# B9_HashBoard.net
KiCad netlist of a schematic drawn in Altium Designer
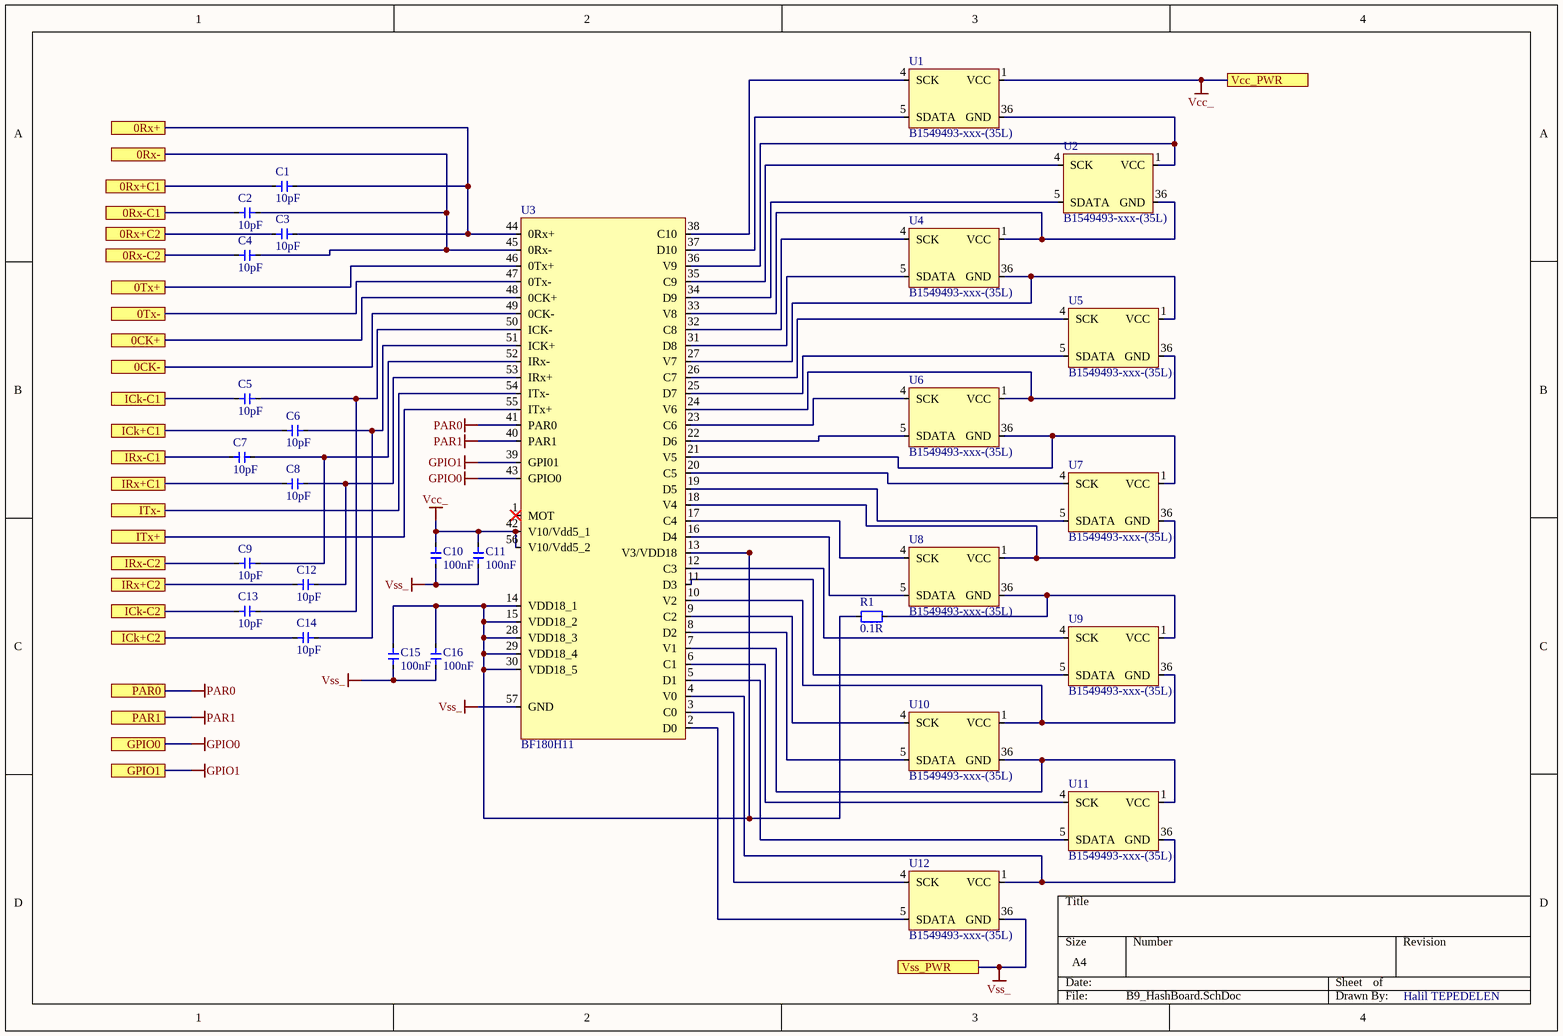
[diagram p0: B9_HashBoard.SchDoc]

(export (version "E")
  (design (tool "Eeschema 10.0.6"))
  (components
    (comp (ref "C1") (value "10pF") (footprint "C-0402R") (libsource (lib "B9_HashBoard") (part "10pF")))
    (comp (ref "C2") (value "10pF") (footprint "C-0402R") (libsource (lib "B9_HashBoard") (part "10pF")))
    (comp (ref "C3") (value "10pF") (footprint "C-0402R") (libsource (lib "B9_HashBoard") (part "10pF")))
    (comp (ref "C4") (value "10pF") (footprint "C-0402R") (libsource (lib "B9_HashBoard") (part "10pF")))
    (comp (ref "C5") (value "10pF") (footprint "C-0402R") (libsource (lib "B9_HashBoard") (part "10pF")))
    (comp (ref "C6") (value "10pF") (footprint "C-0402R") (libsource (lib "B9_HashBoard") (part "10pF")))
    (comp (ref "C7") (value "10pF") (footprint "C-0402R") (libsource (lib "B9_HashBoard") (part "10pF")))
    (comp (ref "C8") (value "10pF") (footprint "C-0402R") (libsource (lib "B9_HashBoard") (part "10pF")))
    (comp (ref "C9") (value "10pF") (footprint "C-0402R") (libsource (lib "B9_HashBoard") (part "10pF")))
    (comp (ref "C10") (value "100nF") (footprint "C-0402R") (libsource (lib "B9_HashBoard") (part "100nF")))
    (comp (ref "C11") (value "100nF") (footprint "C-0402R") (libsource (lib "B9_HashBoard") (part "100nF")))
    (comp (ref "C12") (value "10pF") (footprint "C-0402R") (libsource (lib "B9_HashBoard") (part "10pF")))
    (comp (ref "C13") (value "10pF") (footprint "C-0402R") (libsource (lib "B9_HashBoard") (part "10pF")))
    (comp (ref "C14") (value "10pF") (footprint "C-0402R") (libsource (lib "B9_HashBoard") (part "10pF")))
    (comp (ref "C15") (value "100nF") (footprint "C-0402R") (libsource (lib "B9_HashBoard") (part "100nF")))
    (comp (ref "C16") (value "100nF") (footprint "C-0402R") (libsource (lib "B9_HashBoard") (part "100nF")))
    (comp (ref "R1") (value "0.1R") (footprint "R-0402R") (libsource (lib "B9_HashBoard") (part "0.1R")))
    (comp (ref "U1")
      (value "B1549493-xxx-(35L)")
      (footprint "Bıtfury_Clarke_B1549493")
      (libsource (lib "B9_HashBoard") (part "B1549493-xxx-(35L)"))
    )
    (comp (ref "U2")
      (value "B1549493-xxx-(35L)")
      (footprint "Bıtfury_Clarke_B1549493")
      (libsource (lib "B9_HashBoard") (part "B1549493-xxx-(35L)"))
    )
    (comp (ref "U3")
      (value "BF180H11")
      (footprint "BF180H16")
      (libsource (lib "B9_HashBoard") (part "BF180H11"))
    )
    (comp (ref "U4")
      (value "B1549493-xxx-(35L)")
      (footprint "Bıtfury_Clarke_B1549493")
      (libsource (lib "B9_HashBoard") (part "B1549493-xxx-(35L)"))
    )
    (comp (ref "U5")
      (value "B1549493-xxx-(35L)")
      (footprint "Bıtfury_Clarke_B1549493")
      (libsource (lib "B9_HashBoard") (part "B1549493-xxx-(35L)"))
    )
    (comp (ref "U6")
      (value "B1549493-xxx-(35L)")
      (footprint "Bıtfury_Clarke_B1549493")
      (libsource (lib "B9_HashBoard") (part "B1549493-xxx-(35L)"))
    )
    (comp (ref "U7")
      (value "B1549493-xxx-(35L)")
      (footprint "Bıtfury_Clarke_B1549493")
      (libsource (lib "B9_HashBoard") (part "B1549493-xxx-(35L)"))
    )
    (comp (ref "U8")
      (value "B1549493-xxx-(35L)")
      (footprint "Bıtfury_Clarke_B1549493")
      (libsource (lib "B9_HashBoard") (part "B1549493-xxx-(35L)"))
    )
    (comp (ref "U9")
      (value "B1549493-xxx-(35L)")
      (footprint "Bıtfury_Clarke_B1549493")
      (libsource (lib "B9_HashBoard") (part "B1549493-xxx-(35L)"))
    )
    (comp (ref "U10")
      (value "B1549493-xxx-(35L)")
      (footprint "Bıtfury_Clarke_B1549493")
      (libsource (lib "B9_HashBoard") (part "B1549493-xxx-(35L)"))
    )
    (comp (ref "U11")
      (value "B1549493-xxx-(35L)")
      (footprint "Bıtfury_Clarke_B1549493")
      (libsource (lib "B9_HashBoard") (part "B1549493-xxx-(35L)"))
    )
    (comp (ref "U12")
      (value "B1549493-xxx-(35L)")
      (footprint "Bıtfury_Clarke_B1549493")
      (libsource (lib "B9_HashBoard") (part "B1549493-xxx-(35L)"))
    )
  )
  (nets
    (net (code "1") (name "/0CK+") (class "Default")
      (node (ref "U3") (pin "48") (pinfunction "0CK+_48") (pintype "passive"))
    )
    (net (code "2") (name "/0CK-") (class "Default")
      (node (ref "U3") (pin "49") (pinfunction "0CK-_49") (pintype "passive"))
    )
    (net (code "3") (name "/0Rx+") (class "Default")
      (node (ref "C1") (pin "2") (pinfunction "2_2") (pintype "passive"))
      (node (ref "C3") (pin "2") (pinfunction "2_2") (pintype "passive"))
      (node (ref "U3") (pin "44") (pinfunction "0Rx+_44") (pintype "passive"))
    )
    (net (code "4") (name "/0Rx+C1") (class "Default")
      (node (ref "C1") (pin "1") (pinfunction "1_1") (pintype "passive"))
    )
    (net (code "5") (name "/0Rx+C2") (class "Default")
      (node (ref "C3") (pin "1") (pinfunction "1_1") (pintype "passive"))
    )
    (net (code "6") (name "/0Rx-") (class "Default")
      (node (ref "C2") (pin "2") (pinfunction "2_2") (pintype "passive"))
      (node (ref "C4") (pin "2") (pinfunction "2_2") (pintype "passive"))
      (node (ref "U3") (pin "45") (pinfunction "0Rx-_45") (pintype "passive"))
    )
    (net (code "7") (name "/0Rx-C1") (class "Default")
      (node (ref "C2") (pin "1") (pinfunction "1_1") (pintype "passive"))
    )
    (net (code "8") (name "/0Rx-C2") (class "Default")
      (node (ref "C4") (pin "1") (pinfunction "1_1") (pintype "passive"))
    )
    (net (code "9") (name "/0Tx+") (class "Default")
      (node (ref "U3") (pin "46") (pinfunction "0Tx+_46") (pintype "passive"))
    )
    (net (code "10") (name "/0Tx-") (class "Default")
      (node (ref "U3") (pin "47") (pinfunction "0Tx-_47") (pintype "passive"))
    )
    (net (code "11") (name "/ICk+C1") (class "Default")
      (node (ref "C6") (pin "1") (pinfunction "1_1") (pintype "passive"))
    )
    (net (code "12") (name "/ICk+C2") (class "Default")
      (node (ref "C14") (pin "1") (pinfunction "1_1") (pintype "passive"))
    )
    (net (code "13") (name "/ICk-C1") (class "Default")
      (node (ref "C5") (pin "1") (pinfunction "1_1") (pintype "passive"))
    )
    (net (code "14") (name "/ICk-C2") (class "Default")
      (node (ref "C13") (pin "1") (pinfunction "1_1") (pintype "passive"))
    )
    (net (code "15") (name "/IRx+C1") (class "Default")
      (node (ref "C8") (pin "1") (pinfunction "1_1") (pintype "passive"))
    )
    (net (code "16") (name "/IRx+C2") (class "Default")
      (node (ref "C12") (pin "1") (pinfunction "1_1") (pintype "passive"))
    )
    (net (code "17") (name "/IRx-C1") (class "Default")
      (node (ref "C7") (pin "1") (pinfunction "1_1") (pintype "passive"))
    )
    (net (code "18") (name "/IRx-C2") (class "Default")
      (node (ref "C9") (pin "1") (pinfunction "1_1") (pintype "passive"))
    )
    (net (code "19") (name "/ITx+") (class "Default")
      (node (ref "U3") (pin "55") (pinfunction "ITx+_55") (pintype "passive"))
    )
    (net (code "20") (name "/ITx-") (class "Default")
      (node (ref "U3") (pin "54") (pinfunction "ITx-_54") (pintype "passive"))
    )
    (net (code "21") (name "GPIO0") (class "Default")
      (node (ref "U3") (pin "43") (pinfunction "GPIO0_43") (pintype "passive"))
    )
    (net (code "22") (name "GPIO1") (class "Default")
      (node (ref "U3") (pin "39") (pinfunction "GPI01_39") (pintype "passive"))
    )
    (net (code "23") (name "Net-(U1-GND)") (class "Default")
      (node (ref "U1") (pin "36") (pinfunction "GND_36") (pintype "passive"))
      (node (ref "U2") (pin "1") (pinfunction "VCC_1") (pintype "passive"))
      (node (ref "U3") (pin "36") (pinfunction "V9_36") (pintype "passive"))
    )
    (net (code "24") (name "Net-(U1-SCK)") (class "Default")
      (node (ref "U1") (pin "4") (pinfunction "SCK_4") (pintype "passive"))
      (node (ref "U3") (pin "38") (pinfunction "C10_38") (pintype "passive"))
    )
    (net (code "25") (name "Net-(U1-SDATA)") (class "Default")
      (node (ref "U1") (pin "5") (pinfunction "SDATA_5") (pintype "passive"))
      (node (ref "U3") (pin "37") (pinfunction "D10_37") (pintype "passive"))
    )
    (net (code "26") (name "Net-(U2-GND)") (class "Default")
      (node (ref "U2") (pin "36") (pinfunction "GND_36") (pintype "passive"))
      (node (ref "U3") (pin "33") (pinfunction "V8_33") (pintype "passive"))
      (node (ref "U4") (pin "1") (pinfunction "VCC_1") (pintype "passive"))
    )
    (net (code "27") (name "Net-(U2-SCK)") (class "Default")
      (node (ref "U2") (pin "4") (pinfunction "SCK_4") (pintype "passive"))
      (node (ref "U3") (pin "35") (pinfunction "C9_35") (pintype "passive"))
    )
    (net (code "28") (name "Net-(U2-SDATA)") (class "Default")
      (node (ref "U2") (pin "5") (pinfunction "SDATA_5") (pintype "passive"))
      (node (ref "U3") (pin "34") (pinfunction "D9_34") (pintype "passive"))
    )
    (net (code "29") (name "Net-(U3-C3)") (class "Default")
      (node (ref "U3") (pin "12") (pinfunction "C3_12") (pintype "passive"))
      (node (ref "U9") (pin "4") (pinfunction "SCK_4") (pintype "passive"))
    )
    (net (code "30") (name "Net-(U3-C4)") (class "Default")
      (node (ref "U3") (pin "17") (pinfunction "C4_17") (pintype "passive"))
      (node (ref "U8") (pin "4") (pinfunction "SCK_4") (pintype "passive"))
    )
    (net (code "31") (name "Net-(U3-C5)") (class "Default")
      (node (ref "U3") (pin "20") (pinfunction "C5_20") (pintype "passive"))
      (node (ref "U7") (pin "4") (pinfunction "SCK_4") (pintype "passive"))
    )
    (net (code "32") (name "Net-(U3-C6)") (class "Default")
      (node (ref "U3") (pin "23") (pinfunction "C6_23") (pintype "passive"))
      (node (ref "U6") (pin "4") (pinfunction "SCK_4") (pintype "passive"))
    )
    (net (code "33") (name "Net-(U3-C7)") (class "Default")
      (node (ref "U3") (pin "26") (pinfunction "C7_26") (pintype "passive"))
      (node (ref "U5") (pin "4") (pinfunction "SCK_4") (pintype "passive"))
    )
    (net (code "34") (name "Net-(U3-C8)") (class "Default")
      (node (ref "U3") (pin "32") (pinfunction "C8_32") (pintype "passive"))
      (node (ref "U4") (pin "4") (pinfunction "SCK_4") (pintype "passive"))
    )
    (net (code "35") (name "Net-(U3-D3)") (class "Default")
      (node (ref "U3") (pin "11") (pinfunction "D3_11") (pintype "passive"))
      (node (ref "U9") (pin "5") (pinfunction "SDATA_5") (pintype "passive"))
    )
    (net (code "36") (name "Net-(U3-D4)") (class "Default")
      (node (ref "U3") (pin "16") (pinfunction "D4_16") (pintype "passive"))
      (node (ref "U8") (pin "5") (pinfunction "SDATA_5") (pintype "passive"))
    )
    (net (code "37") (name "Net-(U3-D5)") (class "Default")
      (node (ref "U3") (pin "19") (pinfunction "D5_19") (pintype "passive"))
      (node (ref "U7") (pin "5") (pinfunction "SDATA_5") (pintype "passive"))
    )
    (net (code "38") (name "Net-(U3-D6)") (class "Default")
      (node (ref "U3") (pin "22") (pinfunction "D6_22") (pintype "passive"))
      (node (ref "U6") (pin "5") (pinfunction "SDATA_5") (pintype "passive"))
    )
    (net (code "39") (name "Net-(U3-D7)") (class "Default")
      (node (ref "U3") (pin "25") (pinfunction "D7_25") (pintype "passive"))
      (node (ref "U5") (pin "5") (pinfunction "SDATA_5") (pintype "passive"))
    )
    (net (code "40") (name "Net-(U3-D8)") (class "Default")
      (node (ref "U3") (pin "31") (pinfunction "D8_31") (pintype "passive"))
      (node (ref "U4") (pin "5") (pinfunction "SDATA_5") (pintype "passive"))
    )
    (net (code "41") (name "Net-(U3-ICK+)") (class "Default")
      (node (ref "C14") (pin "2") (pinfunction "2_2") (pintype "passive"))
      (node (ref "C6") (pin "2") (pinfunction "2_2") (pintype "passive"))
      (node (ref "U3") (pin "51") (pinfunction "ICK+_51") (pintype "passive"))
    )
    (net (code "42") (name "Net-(U3-ICK-)") (class "Default")
      (node (ref "C13") (pin "2") (pinfunction "2_2") (pintype "passive"))
      (node (ref "C5") (pin "2") (pinfunction "2_2") (pintype "passive"))
      (node (ref "U3") (pin "50") (pinfunction "ICK-_50") (pintype "passive"))
    )
    (net (code "43") (name "Net-(U3-IRx+)") (class "Default")
      (node (ref "C12") (pin "2") (pinfunction "2_2") (pintype "passive"))
      (node (ref "C8") (pin "2") (pinfunction "2_2") (pintype "passive"))
      (node (ref "U3") (pin "53") (pinfunction "IRx+_53") (pintype "passive"))
    )
    (net (code "44") (name "Net-(U3-IRx-)") (class "Default")
      (node (ref "C7") (pin "2") (pinfunction "2_2") (pintype "passive"))
      (node (ref "C9") (pin "2") (pinfunction "2_2") (pintype "passive"))
      (node (ref "U3") (pin "52") (pinfunction "IRx-_52") (pintype "passive"))
    )
    (net (code "45") (name "Net-(U3-V3{slash}VDD18)") (class "Default")
      (node (ref "C15") (pin "2") (pinfunction "2_2") (pintype "passive"))
      (node (ref "C16") (pin "2") (pinfunction "2_2") (pintype "passive"))
      (node (ref "R1") (pin "1") (pinfunction "1_1") (pintype "passive"))
      (node (ref "U3") (pin "13") (pinfunction "V3/VDD18_13") (pintype "passive"))
      (node (ref "U3") (pin "14") (pinfunction "VDD18_1_14") (pintype "passive"))
      (node (ref "U3") (pin "15") (pinfunction "VDD18_2_15") (pintype "passive"))
      (node (ref "U3") (pin "28") (pinfunction "VDD18_3_28") (pintype "passive"))
      (node (ref "U3") (pin "29") (pinfunction "VDD18_4_29") (pintype "passive"))
      (node (ref "U3") (pin "30") (pinfunction "VDD18_5_30") (pintype "passive"))
    )
    (net (code "46") (name "Net-(U3-V4)") (class "Default")
      (node (ref "U3") (pin "18") (pinfunction "V4_18") (pintype "passive"))
      (node (ref "U7") (pin "36") (pinfunction "GND_36") (pintype "passive"))
      (node (ref "U8") (pin "1") (pinfunction "VCC_1") (pintype "passive"))
    )
    (net (code "47") (name "Net-(U3-V5)") (class "Default")
      (node (ref "U3") (pin "21") (pinfunction "V5_21") (pintype "passive"))
      (node (ref "U6") (pin "36") (pinfunction "GND_36") (pintype "passive"))
      (node (ref "U7") (pin "1") (pinfunction "VCC_1") (pintype "passive"))
    )
    (net (code "48") (name "Net-(U3-V6)") (class "Default")
      (node (ref "U3") (pin "24") (pinfunction "V6_24") (pintype "passive"))
      (node (ref "U5") (pin "36") (pinfunction "GND_36") (pintype "passive"))
      (node (ref "U6") (pin "1") (pinfunction "VCC_1") (pintype "passive"))
    )
    (net (code "49") (name "Net-(U3-V7)") (class "Default")
      (node (ref "U3") (pin "27") (pinfunction "V7_27") (pintype "passive"))
      (node (ref "U4") (pin "36") (pinfunction "GND_36") (pintype "passive"))
      (node (ref "U5") (pin "1") (pinfunction "VCC_1") (pintype "passive"))
    )
    (net (code "50") (name "Net-(U8-GND)") (class "Default")
      (node (ref "R1") (pin "2") (pinfunction "2_2") (pintype "passive"))
      (node (ref "U8") (pin "36") (pinfunction "GND_36") (pintype "passive"))
      (node (ref "U9") (pin "1") (pinfunction "VCC_1") (pintype "passive"))
    )
    (net (code "51") (name "Net-(U10-GND)") (class "Default")
      (node (ref "U10") (pin "36") (pinfunction "GND_36") (pintype "passive"))
      (node (ref "U11") (pin "1") (pinfunction "VCC_1") (pintype "passive"))
      (node (ref "U3") (pin "7") (pinfunction "V1_7") (pintype "passive"))
    )
    (net (code "52") (name "Net-(U10-SCK)") (class "Default")
      (node (ref "U10") (pin "4") (pinfunction "SCK_4") (pintype "passive"))
      (node (ref "U3") (pin "9") (pinfunction "C2_9") (pintype "passive"))
    )
    (net (code "53") (name "Net-(U10-SDATA)") (class "Default")
      (node (ref "U10") (pin "5") (pinfunction "SDATA_5") (pintype "passive"))
      (node (ref "U3") (pin "8") (pinfunction "D2_8") (pintype "passive"))
    )
    (net (code "54") (name "Net-(U10-VCC)") (class "Default")
      (node (ref "U10") (pin "1") (pinfunction "VCC_1") (pintype "passive"))
      (node (ref "U3") (pin "10") (pinfunction "V2_10") (pintype "passive"))
      (node (ref "U9") (pin "36") (pinfunction "GND_36") (pintype "passive"))
    )
    (net (code "55") (name "Net-(U11-GND)") (class "Default")
      (node (ref "U11") (pin "36") (pinfunction "GND_36") (pintype "passive"))
      (node (ref "U12") (pin "1") (pinfunction "VCC_1") (pintype "passive"))
      (node (ref "U3") (pin "4") (pinfunction "V0_4") (pintype "passive"))
    )
    (net (code "56") (name "Net-(U11-SCK)") (class "Default")
      (node (ref "U11") (pin "4") (pinfunction "SCK_4") (pintype "passive"))
      (node (ref "U3") (pin "6") (pinfunction "C1_6") (pintype "passive"))
    )
    (net (code "57") (name "Net-(U11-SDATA)") (class "Default")
      (node (ref "U11") (pin "5") (pinfunction "SDATA_5") (pintype "passive"))
      (node (ref "U3") (pin "5") (pinfunction "D1_5") (pintype "passive"))
    )
    (net (code "58") (name "Net-(U12-SCK)") (class "Default")
      (node (ref "U12") (pin "4") (pinfunction "SCK_4") (pintype "passive"))
      (node (ref "U3") (pin "3") (pinfunction "C0_3") (pintype "passive"))
    )
    (net (code "59") (name "Net-(U12-SDATA)") (class "Default")
      (node (ref "U12") (pin "5") (pinfunction "SDATA_5") (pintype "passive"))
      (node (ref "U3") (pin "2") (pinfunction "D0_2") (pintype "passive"))
    )
    (net (code "60") (name "PAR0") (class "Default")
      (node (ref "U3") (pin "41") (pinfunction "PAR0_41") (pintype "passive"))
    )
    (net (code "61") (name "PAR1") (class "Default")
      (node (ref "U3") (pin "40") (pinfunction "PAR1_40") (pintype "passive"))
    )
    (net (code "62") (name "Vcc_") (class "Default")
      (node (ref "C10") (pin "2") (pinfunction "2_2") (pintype "passive"))
      (node (ref "C11") (pin "2") (pinfunction "2_2") (pintype "passive"))
      (node (ref "U1") (pin "1") (pinfunction "VCC_1") (pintype "passive"))
      (node (ref "U3") (pin "42") (pinfunction "V10/Vdd5_1_42") (pintype "passive"))
      (node (ref "U3") (pin "56") (pinfunction "V10/Vdd5_2_56") (pintype "passive"))
    )
    (net (code "63") (name "Vss_") (class "Default")
      (node (ref "C10") (pin "1") (pinfunction "1_1") (pintype "passive"))
      (node (ref "C11") (pin "1") (pinfunction "1_1") (pintype "passive"))
      (node (ref "C15") (pin "1") (pinfunction "1_1") (pintype "passive"))
      (node (ref "C16") (pin "1") (pinfunction "1_1") (pintype "passive"))
      (node (ref "U12") (pin "36") (pinfunction "GND_36") (pintype "passive"))
      (node (ref "U3") (pin "57") (pinfunction "GND_57") (pintype "passive"))
    )
    (net (code "64") (name "unconnected-(U3-MOT-Pad1)") (class "Default")
      (node (ref "U3") (pin "1") (pinfunction "MOT_1") (pintype "passive+no_connect"))
    )
  )
)
